# Connector.net
KiCad netlist of a schematic drawn in Altium Designer
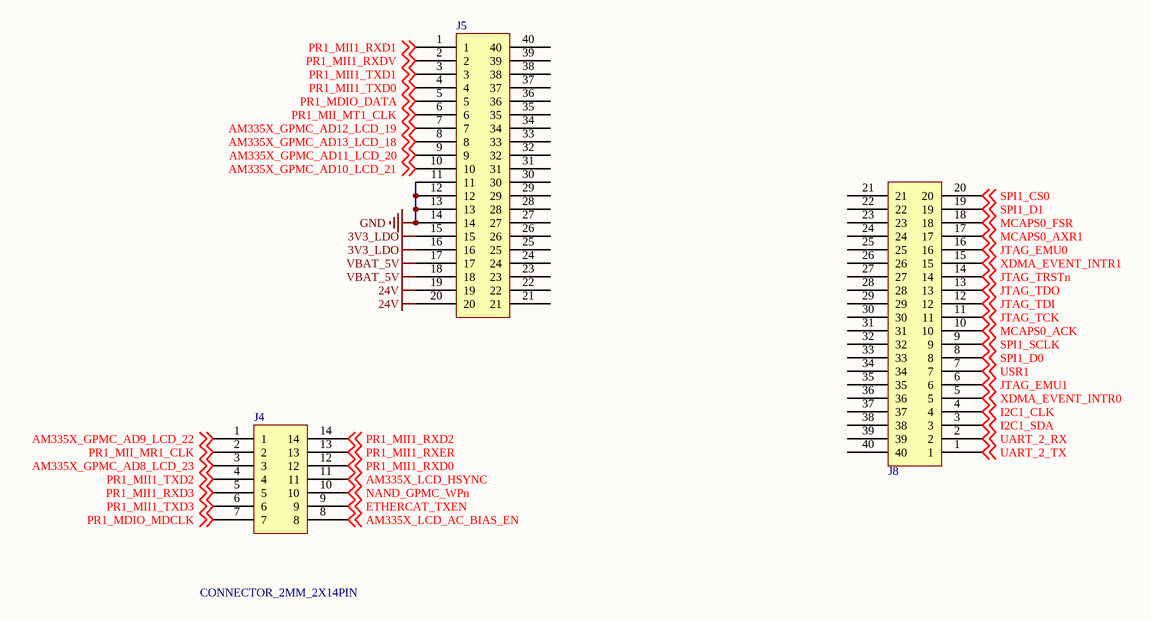
[diagram p0: Connector.SchDoc]

(export (version "E")
  (design (tool "Eeschema 10.0.6"))
  (components
    (comp (ref "J4")
      (value "CONNECTOR_2MM_2X14PIN")
      (footprint "JTAG,0.254_G")
      (libsource (lib "LINUX") (part "CONNECTOR_2MM_2X14PIN"))
    )
    (comp (ref "J5")
      (value "CONNECTOR_2MM_2X20PIN")
      (footprint "JTAG,0.254 double")
      (libsource (lib "") (part "CONNECTOR_2MM_2X20PIN_1"))
    )
    (comp (ref "J8")
      (value "CONNECTOR_2MM_2X20PIN")
      (footprint "JTAG,0.254 double")
      (libsource (lib "LINUX") (part "CONNECTOR_2MM_2X20PIN"))
    )
  )
  (nets
    (net (code "1") (name "3V3_LDO") (class "Default")
      (node (ref "J5") (pin "15") (pinfunction "15_15") (pintype "passive"))
      (node (ref "J5") (pin "16") (pinfunction "16_16") (pintype "passive"))
    )
    (net (code "2") (name "24V") (class "Default")
      (node (ref "J5") (pin "19") (pinfunction "19_19") (pintype "passive"))
      (node (ref "J5") (pin "20") (pinfunction "20_20") (pintype "passive"))
    )
    (net (code "3") (name "AM335X_GPMC_AD8_LCD_23") (class "Default")
      (node (ref "J4") (pin "3") (pinfunction "3_3") (pintype "passive"))
    )
    (net (code "4") (name "AM335X_GPMC_AD9_LCD_22") (class "Default")
      (node (ref "J4") (pin "1") (pinfunction "1_1") (pintype "passive"))
    )
    (net (code "5") (name "AM335X_GPMC_AD10_LCD_21") (class "Default")
      (node (ref "J5") (pin "10") (pinfunction "10_10") (pintype "passive"))
    )
    (net (code "6") (name "AM335X_GPMC_AD11_LCD_20") (class "Default")
      (node (ref "J5") (pin "9") (pinfunction "9_9") (pintype "passive"))
    )
    (net (code "7") (name "AM335X_GPMC_AD12_LCD_19") (class "Default")
      (node (ref "J5") (pin "7") (pinfunction "7_7") (pintype "passive"))
    )
    (net (code "8") (name "AM335X_GPMC_AD13_LCD_18") (class "Default")
      (node (ref "J5") (pin "8") (pinfunction "8_8") (pintype "passive"))
    )
    (net (code "9") (name "AM335X_LCD_AC_BIAS_EN") (class "Default")
      (node (ref "J4") (pin "8") (pinfunction "8_8") (pintype "passive"))
    )
    (net (code "10") (name "AM335X_LCD_HSYNC") (class "Default")
      (node (ref "J4") (pin "11") (pinfunction "11_11") (pintype "passive"))
    )
    (net (code "11") (name "ETHERCAT_TXEN") (class "Default")
      (node (ref "J4") (pin "9") (pinfunction "9_9") (pintype "passive"))
    )
    (net (code "12") (name "GND") (class "Default")
      (node (ref "J5") (pin "11") (pinfunction "11_11") (pintype "passive"))
      (node (ref "J5") (pin "12") (pinfunction "12_12") (pintype "passive"))
      (node (ref "J5") (pin "13") (pinfunction "13_13") (pintype "passive"))
      (node (ref "J5") (pin "14") (pinfunction "14_14") (pintype "passive"))
    )
    (net (code "13") (name "I2C1_CLK") (class "Default")
      (node (ref "J8") (pin "4") (pinfunction "4_4") (pintype "passive"))
    )
    (net (code "14") (name "I2C1_SDA") (class "Default")
      (node (ref "J8") (pin "3") (pinfunction "3_3") (pintype "passive"))
    )
    (net (code "15") (name "JTAG_EMU0") (class "Default")
      (node (ref "J8") (pin "16") (pinfunction "16_16") (pintype "passive"))
    )
    (net (code "16") (name "JTAG_EMU1") (class "Default")
      (node (ref "J8") (pin "6") (pinfunction "6_6") (pintype "passive"))
    )
    (net (code "17") (name "JTAG_TCK") (class "Default")
      (node (ref "J8") (pin "11") (pinfunction "11_11") (pintype "passive"))
    )
    (net (code "18") (name "JTAG_TDI") (class "Default")
      (node (ref "J8") (pin "12") (pinfunction "12_12") (pintype "passive"))
    )
    (net (code "19") (name "JTAG_TDO") (class "Default")
      (node (ref "J8") (pin "13") (pinfunction "13_13") (pintype "passive"))
    )
    (net (code "20") (name "JTAG_TRSTn") (class "Default")
      (node (ref "J8") (pin "14") (pinfunction "14_14") (pintype "passive"))
    )
    (net (code "21") (name "MCAPS0_ACK") (class "Default")
      (node (ref "J8") (pin "10") (pinfunction "10_10") (pintype "passive"))
    )
    (net (code "22") (name "MCAPS0_AXR1") (class "Default")
      (node (ref "J8") (pin "17") (pinfunction "17_17") (pintype "passive"))
    )
    (net (code "23") (name "MCAPS0_FSR") (class "Default")
      (node (ref "J8") (pin "18") (pinfunction "18_18") (pintype "passive"))
    )
    (net (code "24") (name "NAND_GPMC_WPn") (class "Default")
      (node (ref "J4") (pin "10") (pinfunction "10_10") (pintype "passive"))
    )
    (net (code "25") (name "PR1_MDIO_DATA") (class "Default")
      (node (ref "J5") (pin "5") (pinfunction "5_5") (pintype "passive"))
    )
    (net (code "26") (name "PR1_MDIO_MDCLK") (class "Default")
      (node (ref "J4") (pin "7") (pinfunction "7_7") (pintype "passive"))
    )
    (net (code "27") (name "PR1_MII1_RXD0") (class "Default")
      (node (ref "J4") (pin "12") (pinfunction "12_12") (pintype "passive"))
    )
    (net (code "28") (name "PR1_MII1_RXD1") (class "Default")
      (node (ref "J5") (pin "1") (pinfunction "1_1") (pintype "passive"))
    )
    (net (code "29") (name "PR1_MII1_RXD2") (class "Default")
      (node (ref "J4") (pin "14") (pinfunction "14_14") (pintype "passive"))
    )
    (net (code "30") (name "PR1_MII1_RXD3") (class "Default")
      (node (ref "J4") (pin "5") (pinfunction "5_5") (pintype "passive"))
    )
    (net (code "31") (name "PR1_MII1_RXDV") (class "Default")
      (node (ref "J5") (pin "2") (pinfunction "2_2") (pintype "passive"))
    )
    (net (code "32") (name "PR1_MII1_RXER") (class "Default")
      (node (ref "J4") (pin "13") (pinfunction "13_13") (pintype "passive"))
    )
    (net (code "33") (name "PR1_MII1_TXD0") (class "Default")
      (node (ref "J5") (pin "4") (pinfunction "4_4") (pintype "passive"))
    )
    (net (code "34") (name "PR1_MII1_TXD1") (class "Default")
      (node (ref "J5") (pin "3") (pinfunction "3_3") (pintype "passive"))
    )
    (net (code "35") (name "PR1_MII1_TXD2") (class "Default")
      (node (ref "J4") (pin "4") (pinfunction "4_4") (pintype "passive"))
    )
    (net (code "36") (name "PR1_MII1_TXD3") (class "Default")
      (node (ref "J4") (pin "6") (pinfunction "6_6") (pintype "passive"))
    )
    (net (code "37") (name "PR1_MII_MR1_CLK") (class "Default")
      (node (ref "J4") (pin "2") (pinfunction "2_2") (pintype "passive"))
    )
    (net (code "38") (name "PR1_MII_MT1_CLK") (class "Default")
      (node (ref "J5") (pin "6") (pinfunction "6_6") (pintype "passive"))
    )
    (net (code "39") (name "SPI1_CS0") (class "Default")
      (node (ref "J8") (pin "20") (pinfunction "20_20") (pintype "passive"))
    )
    (net (code "40") (name "SPI1_D0") (class "Default")
      (node (ref "J8") (pin "8") (pinfunction "8_8") (pintype "passive"))
    )
    (net (code "41") (name "SPI1_D1") (class "Default")
      (node (ref "J8") (pin "19") (pinfunction "19_19") (pintype "passive"))
    )
    (net (code "42") (name "SPI1_SCLK") (class "Default")
      (node (ref "J8") (pin "9") (pinfunction "9_9") (pintype "passive"))
    )
    (net (code "43") (name "UART_2_RX") (class "Default")
      (node (ref "J8") (pin "2") (pinfunction "2_2") (pintype "passive"))
    )
    (net (code "44") (name "UART_2_TX") (class "Default")
      (node (ref "J8") (pin "1") (pinfunction "1_1") (pintype "passive"))
    )
    (net (code "45") (name "USR1") (class "Default")
      (node (ref "J8") (pin "7") (pinfunction "7_7") (pintype "passive"))
    )
    (net (code "46") (name "VBAT_5V") (class "Default")
      (node (ref "J5") (pin "17") (pinfunction "17_17") (pintype "passive"))
      (node (ref "J5") (pin "18") (pinfunction "18_18") (pintype "passive"))
    )
    (net (code "47") (name "XDMA_EVENT_INTR0") (class "Default")
      (node (ref "J8") (pin "5") (pinfunction "5_5") (pintype "passive"))
    )
    (net (code "48") (name "XDMA_EVENT_INTR1") (class "Default")
      (node (ref "J8") (pin "15") (pinfunction "15_15") (pintype "passive"))
    )
    (net (code "49") (name "unconnected-(J5-Pad21)") (class "Default")
      (node (ref "J5") (pin "21") (pinfunction "21_21") (pintype "passive"))
    )
    (net (code "50") (name "unconnected-(J5-Pad22)") (class "Default")
      (node (ref "J5") (pin "22") (pinfunction "22_22") (pintype "passive"))
    )
    (net (code "51") (name "unconnected-(J5-Pad23)") (class "Default")
      (node (ref "J5") (pin "23") (pinfunction "23_23") (pintype "passive"))
    )
    (net (code "52") (name "unconnected-(J5-Pad24)") (class "Default")
      (node (ref "J5") (pin "24") (pinfunction "24_24") (pintype "passive"))
    )
    (net (code "53") (name "unconnected-(J5-Pad25)") (class "Default")
      (node (ref "J5") (pin "25") (pinfunction "25_25") (pintype "passive"))
    )
    (net (code "54") (name "unconnected-(J5-Pad26)") (class "Default")
      (node (ref "J5") (pin "26") (pinfunction "26_26") (pintype "passive"))
    )
    (net (code "55") (name "unconnected-(J5-Pad27)") (class "Default")
      (node (ref "J5") (pin "27") (pinfunction "27_27") (pintype "passive"))
    )
    (net (code "56") (name "unconnected-(J5-Pad28)") (class "Default")
      (node (ref "J5") (pin "28") (pinfunction "28_28") (pintype "passive"))
    )
    (net (code "57") (name "unconnected-(J5-Pad29)") (class "Default")
      (node (ref "J5") (pin "29") (pinfunction "29_29") (pintype "passive"))
    )
    (net (code "58") (name "unconnected-(J5-Pad30)") (class "Default")
      (node (ref "J5") (pin "30") (pinfunction "30_30") (pintype "passive"))
    )
    (net (code "59") (name "unconnected-(J5-Pad31)") (class "Default")
      (node (ref "J5") (pin "31") (pinfunction "31_31") (pintype "passive"))
    )
    (net (code "60") (name "unconnected-(J5-Pad32)") (class "Default")
      (node (ref "J5") (pin "32") (pinfunction "32_32") (pintype "passive"))
    )
    (net (code "61") (name "unconnected-(J5-Pad33)") (class "Default")
      (node (ref "J5") (pin "33") (pinfunction "33_33") (pintype "passive"))
    )
    (net (code "62") (name "unconnected-(J5-Pad34)") (class "Default")
      (node (ref "J5") (pin "34") (pinfunction "34_34") (pintype "passive"))
    )
    (net (code "63") (name "unconnected-(J5-Pad35)") (class "Default")
      (node (ref "J5") (pin "35") (pinfunction "35_35") (pintype "passive"))
    )
    (net (code "64") (name "unconnected-(J5-Pad36)") (class "Default")
      (node (ref "J5") (pin "36") (pinfunction "36_36") (pintype "passive"))
    )
    (net (code "65") (name "unconnected-(J5-Pad37)") (class "Default")
      (node (ref "J5") (pin "37") (pinfunction "37_37") (pintype "passive"))
    )
    (net (code "66") (name "unconnected-(J5-Pad38)") (class "Default")
      (node (ref "J5") (pin "38") (pinfunction "38_38") (pintype "passive"))
    )
    (net (code "67") (name "unconnected-(J5-Pad39)") (class "Default")
      (node (ref "J5") (pin "39") (pinfunction "39_39") (pintype "passive"))
    )
    (net (code "68") (name "unconnected-(J5-Pad40)") (class "Default")
      (node (ref "J5") (pin "40") (pinfunction "40_40") (pintype "passive"))
    )
    (net (code "69") (name "unconnected-(J8-Pad21)") (class "Default")
      (node (ref "J8") (pin "21") (pinfunction "21_21") (pintype "passive"))
    )
    (net (code "70") (name "unconnected-(J8-Pad22)") (class "Default")
      (node (ref "J8") (pin "22") (pinfunction "22_22") (pintype "passive"))
    )
    (net (code "71") (name "unconnected-(J8-Pad23)") (class "Default")
      (node (ref "J8") (pin "23") (pinfunction "23_23") (pintype "passive"))
    )
    (net (code "72") (name "unconnected-(J8-Pad24)") (class "Default")
      (node (ref "J8") (pin "24") (pinfunction "24_24") (pintype "passive"))
    )
    (net (code "73") (name "unconnected-(J8-Pad25)") (class "Default")
      (node (ref "J8") (pin "25") (pinfunction "25_25") (pintype "passive"))
    )
    (net (code "74") (name "unconnected-(J8-Pad26)") (class "Default")
      (node (ref "J8") (pin "26") (pinfunction "26_26") (pintype "passive"))
    )
    (net (code "75") (name "unconnected-(J8-Pad27)") (class "Default")
      (node (ref "J8") (pin "27") (pinfunction "27_27") (pintype "passive"))
    )
    (net (code "76") (name "unconnected-(J8-Pad28)") (class "Default")
      (node (ref "J8") (pin "28") (pinfunction "28_28") (pintype "passive"))
    )
    (net (code "77") (name "unconnected-(J8-Pad29)") (class "Default")
      (node (ref "J8") (pin "29") (pinfunction "29_29") (pintype "passive"))
    )
    (net (code "78") (name "unconnected-(J8-Pad30)") (class "Default")
      (node (ref "J8") (pin "30") (pinfunction "30_30") (pintype "passive"))
    )
    (net (code "79") (name "unconnected-(J8-Pad31)") (class "Default")
      (node (ref "J8") (pin "31") (pinfunction "31_31") (pintype "passive"))
    )
    (net (code "80") (name "unconnected-(J8-Pad32)") (class "Default")
      (node (ref "J8") (pin "32") (pinfunction "32_32") (pintype "passive"))
    )
    (net (code "81") (name "unconnected-(J8-Pad33)") (class "Default")
      (node (ref "J8") (pin "33") (pinfunction "33_33") (pintype "passive"))
    )
    (net (code "82") (name "unconnected-(J8-Pad34)") (class "Default")
      (node (ref "J8") (pin "34") (pinfunction "34_34") (pintype "passive"))
    )
    (net (code "83") (name "unconnected-(J8-Pad35)") (class "Default")
      (node (ref "J8") (pin "35") (pinfunction "35_35") (pintype "passive"))
    )
    (net (code "84") (name "unconnected-(J8-Pad36)") (class "Default")
      (node (ref "J8") (pin "36") (pinfunction "36_36") (pintype "passive"))
    )
    (net (code "85") (name "unconnected-(J8-Pad37)") (class "Default")
      (node (ref "J8") (pin "37") (pinfunction "37_37") (pintype "passive"))
    )
    (net (code "86") (name "unconnected-(J8-Pad38)") (class "Default")
      (node (ref "J8") (pin "38") (pinfunction "38_38") (pintype "passive"))
    )
    (net (code "87") (name "unconnected-(J8-Pad39)") (class "Default")
      (node (ref "J8") (pin "39") (pinfunction "39_39") (pintype "passive"))
    )
    (net (code "88") (name "unconnected-(J8-Pad40)") (class "Default")
      (node (ref "J8") (pin "40") (pinfunction "40_40") (pintype "passive"))
    )
  )
)
